# kgopalak_SMD.net
KiCad netlist of a schematic drawn in EAGLE
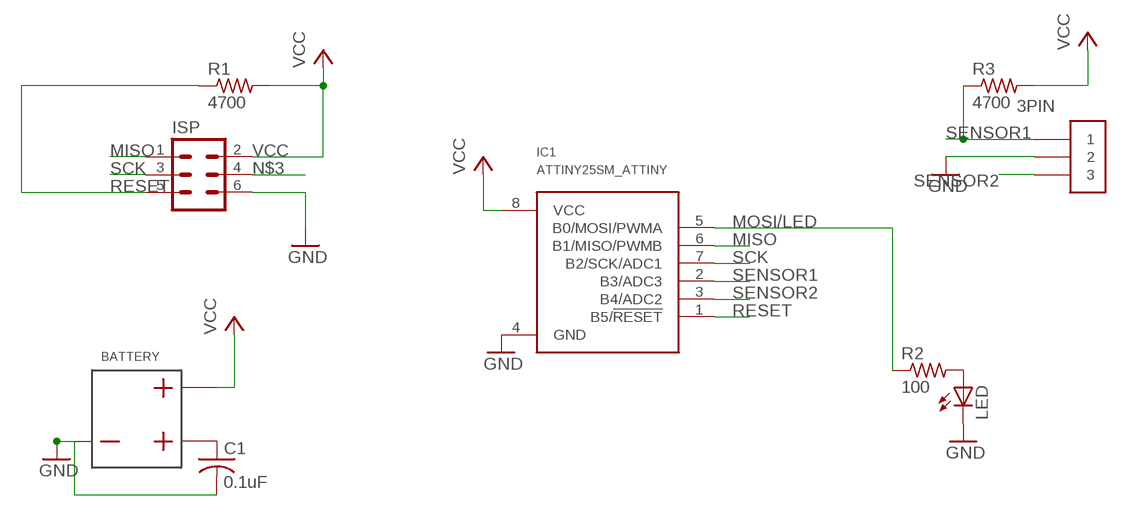
[diagram p0: schematic, sheet 1]

(export (version "E")
  (design (tool "Eeschema 10.0.6"))
  (components
    (comp (ref "3PIN")
      (value "3PINCONSM_3PIN")
      (footprint "eagle-import:SM3PIN")
      (libsource (lib "eagle-import") (part "3PINCONSM_3PIN"))
    )
    (comp (ref "BATTERY")
      (value "BATTERYSM_BA2032")
      (footprint "eagle-import:BA2032SM")
      (libsource (lib "eagle-import") (part "BATTERYSM_BA2032"))
    )
    (comp (ref "C1")
      (value "0.1uF")
      (footprint "eagle-import:C0402")
      (libsource (lib "eagle-import") (part "CAPACITORSM_CAP"))
    )
    (comp (ref "IC1")
      (value "ATTINY25SM_ATTINY")
      (footprint "eagle-import:8S1")
      (libsource (lib "eagle-import") (part "ATTINY25SM_ATTINY"))
    )
    (comp (ref "ISP")
      (value "6PINCON_ISPSM_6PIN")
      (footprint "eagle-import:SM6PIN")
      (libsource (lib "eagle-import") (part "6PINCON_ISPSM_6PIN"))
    )
    (comp (ref "LED")
      (value "LEDSMLED")
      (footprint "eagle-import:CHIPLED_0603")
      (libsource (lib "eagle-import") (part "LEDSMLED"))
    )
    (comp (ref "R1")
      (value "4700")
      (footprint "eagle-import:R0402")
      (libsource (lib "eagle-import") (part "RESISTORSMRESISTOR"))
    )
    (comp (ref "R2")
      (value "100")
      (footprint "eagle-import:R0402")
      (libsource (lib "eagle-import") (part "RESISTORSMRESISTOR"))
    )
    (comp (ref "R3")
      (value "4700")
      (footprint "eagle-import:R0402")
      (libsource (lib "eagle-import") (part "RESISTORSMRESISTOR"))
    )
  )
  (nets
    (net (code "1") (name "/MISO") (class "Default")
      (node (ref "IC1") (pin "6") (pinfunction "B1/MISO/PWMB_6") (pintype "bidirectional"))
      (node (ref "ISP") (pin "1") (pinfunction "1_1") (pintype "bidirectional"))
    )
    (net (code "2") (name "/MOSI{slash}LED") (class "Default")
      (node (ref "IC1") (pin "5") (pinfunction "B0/MOSI/PWMA_5") (pintype "bidirectional"))
      (node (ref "R2") (pin "1") (pinfunction "1_1") (pintype "bidirectional"))
    )
    (net (code "3") (name "/N$3") (class "Default")
      (node (ref "ISP") (pin "4") (pinfunction "4_4") (pintype "bidirectional"))
    )
    (net (code "4") (name "/RESET") (class "Default")
      (node (ref "IC1") (pin "1") (pinfunction "B5/~{RESET}_1") (pintype "bidirectional"))
      (node (ref "ISP") (pin "5") (pinfunction "5_5") (pintype "bidirectional"))
      (node (ref "R1") (pin "1") (pinfunction "1_1") (pintype "bidirectional"))
    )
    (net (code "5") (name "/SCK") (class "Default")
      (node (ref "IC1") (pin "7") (pinfunction "B2/SCK/ADC1_7") (pintype "bidirectional"))
      (node (ref "ISP") (pin "3") (pinfunction "3_3") (pintype "bidirectional"))
    )
    (net (code "6") (name "/SENSOR1") (class "Default")
      (node (ref "3PIN") (pin "1") (pinfunction "1_1") (pintype "bidirectional"))
      (node (ref "IC1") (pin "2") (pinfunction "B3/ADC3_2") (pintype "bidirectional"))
      (node (ref "R3") (pin "1") (pinfunction "1_1") (pintype "bidirectional"))
    )
    (net (code "7") (name "/SENSOR2") (class "Default")
      (node (ref "3PIN") (pin "3") (pinfunction "3_3") (pintype "bidirectional"))
      (node (ref "IC1") (pin "3") (pinfunction "B4/ADC2_3") (pintype "bidirectional"))
    )
    (net (code "8") (name "GND") (class "Default")
      (node (ref "3PIN") (pin "2") (pinfunction "2_2") (pintype "bidirectional"))
      (node (ref "BATTERY") (pin "1") (pinfunction "P$1_1") (pintype "bidirectional"))
      (node (ref "C1") (pin "2") (pinfunction "2_2") (pintype "bidirectional"))
      (node (ref "IC1") (pin "4") (pinfunction "GND_4") (pintype "bidirectional"))
      (node (ref "ISP") (pin "6") (pinfunction "6_6") (pintype "bidirectional"))
      (node (ref "LED") (pin "C") (pinfunction "C_C") (pintype "bidirectional"))
    )
    (net (code "9") (name "Net-(BATTERY-P$3)") (class "Default")
      (node (ref "BATTERY") (pin "3") (pinfunction "P$3_3") (pintype "bidirectional"))
      (node (ref "C1") (pin "1") (pinfunction "1_1") (pintype "bidirectional"))
    )
    (net (code "10") (name "Net-(LED-PadA)") (class "Default")
      (node (ref "LED") (pin "A") (pinfunction "A_A") (pintype "bidirectional"))
      (node (ref "R2") (pin "2") (pinfunction "2_2") (pintype "bidirectional"))
    )
    (net (code "11") (name "VCC") (class "Default")
      (node (ref "BATTERY") (pin "2") (pinfunction "P$2_2") (pintype "bidirectional"))
      (node (ref "IC1") (pin "8") (pinfunction "VCC_8") (pintype "bidirectional"))
      (node (ref "ISP") (pin "2") (pinfunction "2_2") (pintype "bidirectional"))
      (node (ref "R1") (pin "2") (pinfunction "2_2") (pintype "bidirectional"))
      (node (ref "R3") (pin "2") (pinfunction "2_2") (pintype "bidirectional"))
    )
  )
)
